# XBee.net
KiCad netlist of a schematic drawn in EAGLE
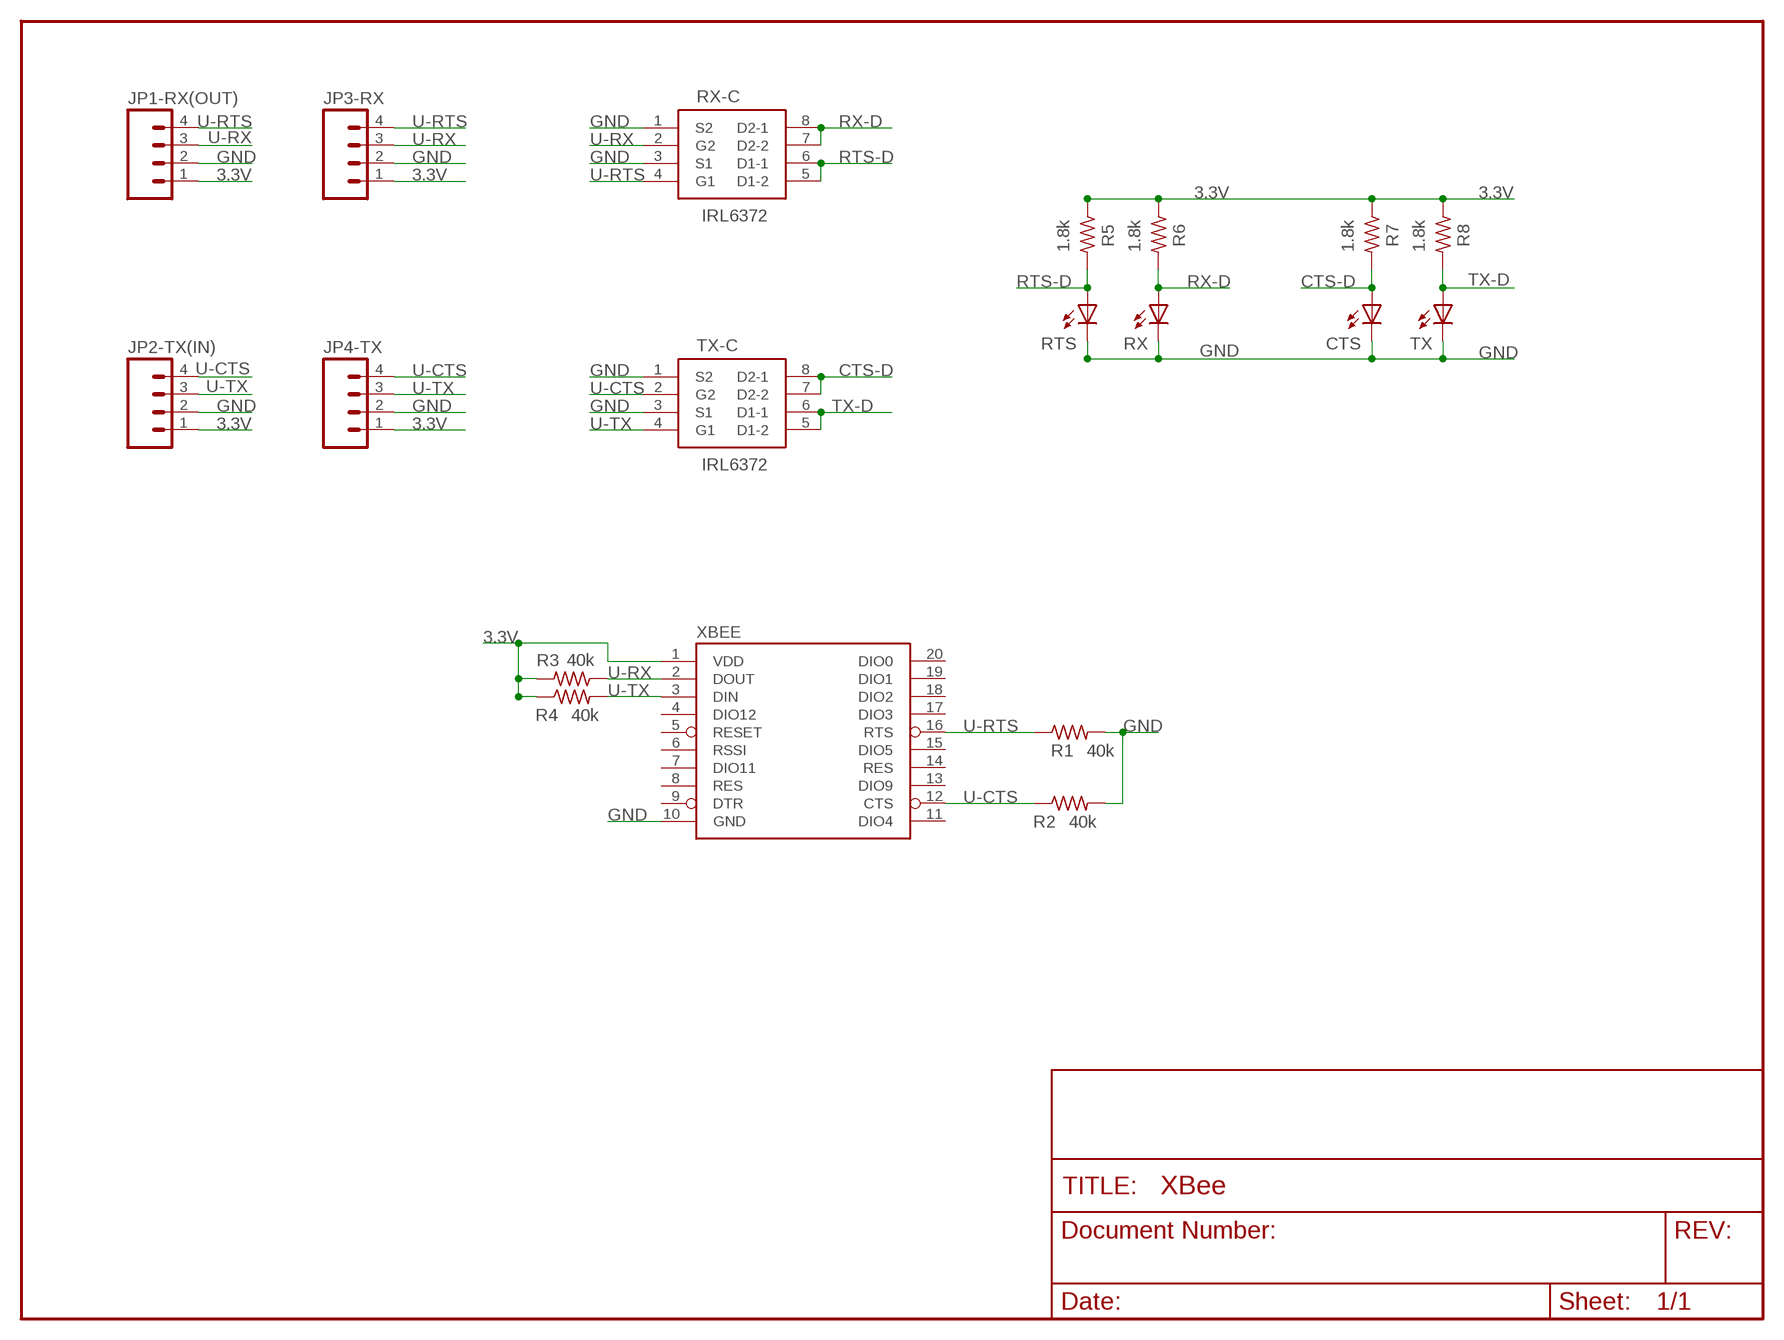
[diagram p0: schematic, sheet 1]

(export (version "E")
  (design (tool "Eeschema 10.0.6"))
  (components
    (comp (ref "CTS")
      (value "LED3MM")
      (footprint "eagle-import:LED3MM")
      (libsource (lib "eagle-import") (part "LED3MM"))
    )
    (comp (ref "JP1-RX(OUT)")
      (value "M04LOCK_LONGPADS")
      (footprint "eagle-import:1X04_LOCK_LONGPADS")
      (libsource (lib "eagle-import") (part "M04LOCK_LONGPADS"))
    )
    (comp (ref "JP2-TX(IN)")
      (value "M04LOCK_LONGPADS")
      (footprint "eagle-import:1X04_LOCK_LONGPADS")
      (libsource (lib "eagle-import") (part "M04LOCK_LONGPADS"))
    )
    (comp (ref "JP3-RX")
      (value "M04LOCK_LONGPADS")
      (footprint "eagle-import:1X04_LOCK_LONGPADS")
      (libsource (lib "eagle-import") (part "M04LOCK_LONGPADS"))
    )
    (comp (ref "JP4-TX")
      (value "M04LOCK_LONGPADS")
      (footprint "eagle-import:1X04_LOCK_LONGPADS")
      (libsource (lib "eagle-import") (part "M04LOCK_LONGPADS"))
    )
    (comp (ref "R1")
      (value "40k")
      (footprint "eagle-import:0204_7")
      (libsource (lib "eagle-import") (part "R-US_0204/7"))
    )
    (comp (ref "R2")
      (value "40k")
      (footprint "eagle-import:0204_7")
      (libsource (lib "eagle-import") (part "R-US_0204/7"))
    )
    (comp (ref "R3")
      (value "40k")
      (footprint "eagle-import:0204_7")
      (libsource (lib "eagle-import") (part "R-US_0204/7"))
    )
    (comp (ref "R4")
      (value "40k")
      (footprint "eagle-import:0204_7")
      (libsource (lib "eagle-import") (part "R-US_0204/7"))
    )
    (comp (ref "R5")
      (value "1.8k")
      (footprint "eagle-import:0204_7")
      (libsource (lib "eagle-import") (part "R-US_0204/7"))
    )
    (comp (ref "R6")
      (value "1.8k")
      (footprint "eagle-import:0204_7")
      (libsource (lib "eagle-import") (part "R-US_0204/7"))
    )
    (comp (ref "R7")
      (value "1.8k")
      (footprint "eagle-import:0204_7")
      (libsource (lib "eagle-import") (part "R-US_0204/7"))
    )
    (comp (ref "R8")
      (value "1.8k")
      (footprint "eagle-import:0204_7")
      (libsource (lib "eagle-import") (part "R-US_0204/7"))
    )
    (comp (ref "RTS")
      (value "LED3MM")
      (footprint "eagle-import:LED3MM")
      (libsource (lib "eagle-import") (part "LED3MM"))
    )
    (comp (ref "RX")
      (value "LED3MM")
      (footprint "eagle-import:LED3MM")
      (libsource (lib "eagle-import") (part "LED3MM"))
    )
    (comp (ref "RX-C")
      (value "IRL6372")
      (footprint "eagle-import:SO08-LARGE-PAD-AZ")
      (libsource (lib "eagle-import") (part "IRL6372_DUAL_MOSFET"))
    )
    (comp (ref "TX")
      (value "LED3MM")
      (footprint "eagle-import:LED3MM")
      (libsource (lib "eagle-import") (part "LED3MM"))
    )
    (comp (ref "TX-C")
      (value "IRL6372")
      (footprint "eagle-import:SO08-LARGE-PAD-AZ")
      (libsource (lib "eagle-import") (part "IRL6372_DUAL_MOSFET"))
    )
    (comp (ref "XBEE")
      (value "XBEELOCK-SMALL-PRINT")
      (footprint "eagle-import:XBEE-1_LOCK")
      (libsource (lib "eagle-import") (part "XBEELOCK-SMALL-PRINT"))
    )
  )
  (nets
    (net (code "1") (name "/3.3V") (class "Default")
      (node (ref "JP1-RX(OUT)") (pin "1") (pinfunction "1_1") (pintype "passive"))
      (node (ref "JP2-TX(IN)") (pin "1") (pinfunction "1_1") (pintype "passive"))
      (node (ref "JP3-RX") (pin "1") (pinfunction "1_1") (pintype "passive"))
      (node (ref "JP4-TX") (pin "1") (pinfunction "1_1") (pintype "passive"))
      (node (ref "R3") (pin "2") (pinfunction "2_2") (pintype "passive"))
      (node (ref "R4") (pin "1") (pinfunction "1_1") (pintype "passive"))
      (node (ref "R5") (pin "1") (pinfunction "1_1") (pintype "passive"))
      (node (ref "R6") (pin "1") (pinfunction "1_1") (pintype "passive"))
      (node (ref "R7") (pin "1") (pinfunction "1_1") (pintype "passive"))
      (node (ref "R8") (pin "1") (pinfunction "1_1") (pintype "passive"))
      (node (ref "XBEE") (pin "1") (pinfunction "VDD_1") (pintype "power_in"))
    )
    (net (code "2") (name "/CTS-D") (class "Default")
      (node (ref "CTS") (pin "A") (pinfunction "A_A") (pintype "passive"))
      (node (ref "R7") (pin "2") (pinfunction "2_2") (pintype "passive"))
      (node (ref "TX-C") (pin "7") (pinfunction "D2-2_7") (pintype "bidirectional"))
      (node (ref "TX-C") (pin "8") (pinfunction "D2-1_8") (pintype "bidirectional"))
    )
    (net (code "3") (name "/GND") (class "Default")
      (node (ref "CTS") (pin "K") (pinfunction "C_K") (pintype "passive"))
      (node (ref "JP1-RX(OUT)") (pin "2") (pinfunction "2_2") (pintype "passive"))
      (node (ref "JP2-TX(IN)") (pin "2") (pinfunction "2_2") (pintype "passive"))
      (node (ref "JP3-RX") (pin "2") (pinfunction "2_2") (pintype "passive"))
      (node (ref "JP4-TX") (pin "2") (pinfunction "2_2") (pintype "passive"))
      (node (ref "R1") (pin "2") (pinfunction "2_2") (pintype "passive"))
      (node (ref "R2") (pin "2") (pinfunction "2_2") (pintype "passive"))
      (node (ref "RTS") (pin "K") (pinfunction "C_K") (pintype "passive"))
      (node (ref "RX") (pin "K") (pinfunction "C_K") (pintype "passive"))
      (node (ref "RX-C") (pin "1") (pinfunction "S2_1") (pintype "bidirectional"))
      (node (ref "RX-C") (pin "3") (pinfunction "S1_3") (pintype "bidirectional"))
      (node (ref "TX") (pin "K") (pinfunction "C_K") (pintype "passive"))
      (node (ref "TX-C") (pin "1") (pinfunction "S2_1") (pintype "bidirectional"))
      (node (ref "TX-C") (pin "3") (pinfunction "S1_3") (pintype "bidirectional"))
      (node (ref "XBEE") (pin "10") (pinfunction "GND_10") (pintype "power_in"))
    )
    (net (code "4") (name "/RTS-D") (class "Default")
      (node (ref "R5") (pin "2") (pinfunction "2_2") (pintype "passive"))
      (node (ref "RTS") (pin "A") (pinfunction "A_A") (pintype "passive"))
      (node (ref "RX-C") (pin "5") (pinfunction "D1-2_5") (pintype "bidirectional"))
      (node (ref "RX-C") (pin "6") (pinfunction "D1-1_6") (pintype "bidirectional"))
    )
    (net (code "5") (name "/RX-D") (class "Default")
      (node (ref "R6") (pin "2") (pinfunction "2_2") (pintype "passive"))
      (node (ref "RX") (pin "A") (pinfunction "A_A") (pintype "passive"))
      (node (ref "RX-C") (pin "7") (pinfunction "D2-2_7") (pintype "bidirectional"))
      (node (ref "RX-C") (pin "8") (pinfunction "D2-1_8") (pintype "bidirectional"))
    )
    (net (code "6") (name "/TX-D") (class "Default")
      (node (ref "R8") (pin "2") (pinfunction "2_2") (pintype "passive"))
      (node (ref "TX") (pin "A") (pinfunction "A_A") (pintype "passive"))
      (node (ref "TX-C") (pin "5") (pinfunction "D1-2_5") (pintype "bidirectional"))
      (node (ref "TX-C") (pin "6") (pinfunction "D1-1_6") (pintype "bidirectional"))
    )
    (net (code "7") (name "/U-CTS") (class "Default")
      (node (ref "JP2-TX(IN)") (pin "4") (pinfunction "4_4") (pintype "passive"))
      (node (ref "JP4-TX") (pin "4") (pinfunction "4_4") (pintype "passive"))
      (node (ref "R2") (pin "1") (pinfunction "1_1") (pintype "passive"))
      (node (ref "TX-C") (pin "2") (pinfunction "G2_2") (pintype "input"))
      (node (ref "XBEE") (pin "12") (pinfunction "CTS_12") (pintype "output"))
    )
    (net (code "8") (name "/U-RTS") (class "Default")
      (node (ref "JP1-RX(OUT)") (pin "4") (pinfunction "4_4") (pintype "passive"))
      (node (ref "JP3-RX") (pin "4") (pinfunction "4_4") (pintype "passive"))
      (node (ref "R1") (pin "1") (pinfunction "1_1") (pintype "passive"))
      (node (ref "RX-C") (pin "4") (pinfunction "G1_4") (pintype "input"))
      (node (ref "XBEE") (pin "16") (pinfunction "RTS_16") (pintype "input"))
    )
    (net (code "9") (name "/U-RX") (class "Default")
      (node (ref "JP1-RX(OUT)") (pin "3") (pinfunction "3_3") (pintype "passive"))
      (node (ref "JP3-RX") (pin "3") (pinfunction "3_3") (pintype "passive"))
      (node (ref "R3") (pin "1") (pinfunction "1_1") (pintype "passive"))
      (node (ref "RX-C") (pin "2") (pinfunction "G2_2") (pintype "input"))
      (node (ref "XBEE") (pin "2") (pinfunction "DOUT_2") (pintype "output"))
    )
    (net (code "10") (name "/U-TX") (class "Default")
      (node (ref "JP2-TX(IN)") (pin "3") (pinfunction "3_3") (pintype "passive"))
      (node (ref "JP4-TX") (pin "3") (pinfunction "3_3") (pintype "passive"))
      (node (ref "R4") (pin "2") (pinfunction "2_2") (pintype "passive"))
      (node (ref "TX-C") (pin "4") (pinfunction "G1_4") (pintype "input"))
      (node (ref "XBEE") (pin "3") (pinfunction "DIN_3") (pintype "input"))
    )
    (net (code "11") (name "unconnected-(XBEE-DIO0-Pad20)") (class "Default")
      (node (ref "XBEE") (pin "20") (pinfunction "DIO0_20") (pintype "bidirectional"))
    )
    (net (code "12") (name "unconnected-(XBEE-DIO1-Pad19)") (class "Default")
      (node (ref "XBEE") (pin "19") (pinfunction "DIO1_19") (pintype "bidirectional"))
    )
    (net (code "13") (name "unconnected-(XBEE-DIO2-Pad18)") (class "Default")
      (node (ref "XBEE") (pin "18") (pinfunction "DIO2_18") (pintype "bidirectional"))
    )
    (net (code "14") (name "unconnected-(XBEE-DIO3-Pad17)") (class "Default")
      (node (ref "XBEE") (pin "17") (pinfunction "DIO3_17") (pintype "bidirectional"))
    )
    (net (code "15") (name "unconnected-(XBEE-DIO4-Pad11)") (class "Default")
      (node (ref "XBEE") (pin "11") (pinfunction "DIO4_11") (pintype "bidirectional"))
    )
    (net (code "16") (name "unconnected-(XBEE-DIO5-Pad15)") (class "Default")
      (node (ref "XBEE") (pin "15") (pinfunction "DIO5_15") (pintype "bidirectional"))
    )
    (net (code "17") (name "unconnected-(XBEE-DIO9-Pad13)") (class "Default")
      (node (ref "XBEE") (pin "13") (pinfunction "DIO9_13") (pintype "bidirectional"))
    )
    (net (code "18") (name "unconnected-(XBEE-DIO11-Pad7)") (class "Default")
      (node (ref "XBEE") (pin "7") (pinfunction "DIO11_7") (pintype "bidirectional"))
    )
    (net (code "19") (name "unconnected-(XBEE-DIO12-Pad4)") (class "Default")
      (node (ref "XBEE") (pin "4") (pinfunction "DIO12_4") (pintype "bidirectional"))
    )
    (net (code "20") (name "unconnected-(XBEE-DTR-Pad9)") (class "Default")
      (node (ref "XBEE") (pin "9") (pinfunction "DTR_9") (pintype "bidirectional"))
    )
    (net (code "21") (name "unconnected-(XBEE-RES-Pad8)") (class "Default")
      (node (ref "XBEE") (pin "8") (pinfunction "RES_8") (pintype "bidirectional"))
    )
    (net (code "22") (name "unconnected-(XBEE-RES-Pad14)") (class "Default")
      (node (ref "XBEE") (pin "14") (pinfunction "RES_14") (pintype "bidirectional"))
    )
    (net (code "23") (name "unconnected-(XBEE-RESET-Pad5)") (class "Default")
      (node (ref "XBEE") (pin "5") (pinfunction "RESET_5") (pintype "input"))
    )
    (net (code "24") (name "unconnected-(XBEE-RSSI-Pad6)") (class "Default")
      (node (ref "XBEE") (pin "6") (pinfunction "RSSI_6") (pintype "bidirectional"))
    )
  )
)
